# ProPrj_esp32s3-ai-chat_audio_2024-08-31.net
KiCad netlist of a schematic drawn in EasyEDA Pro
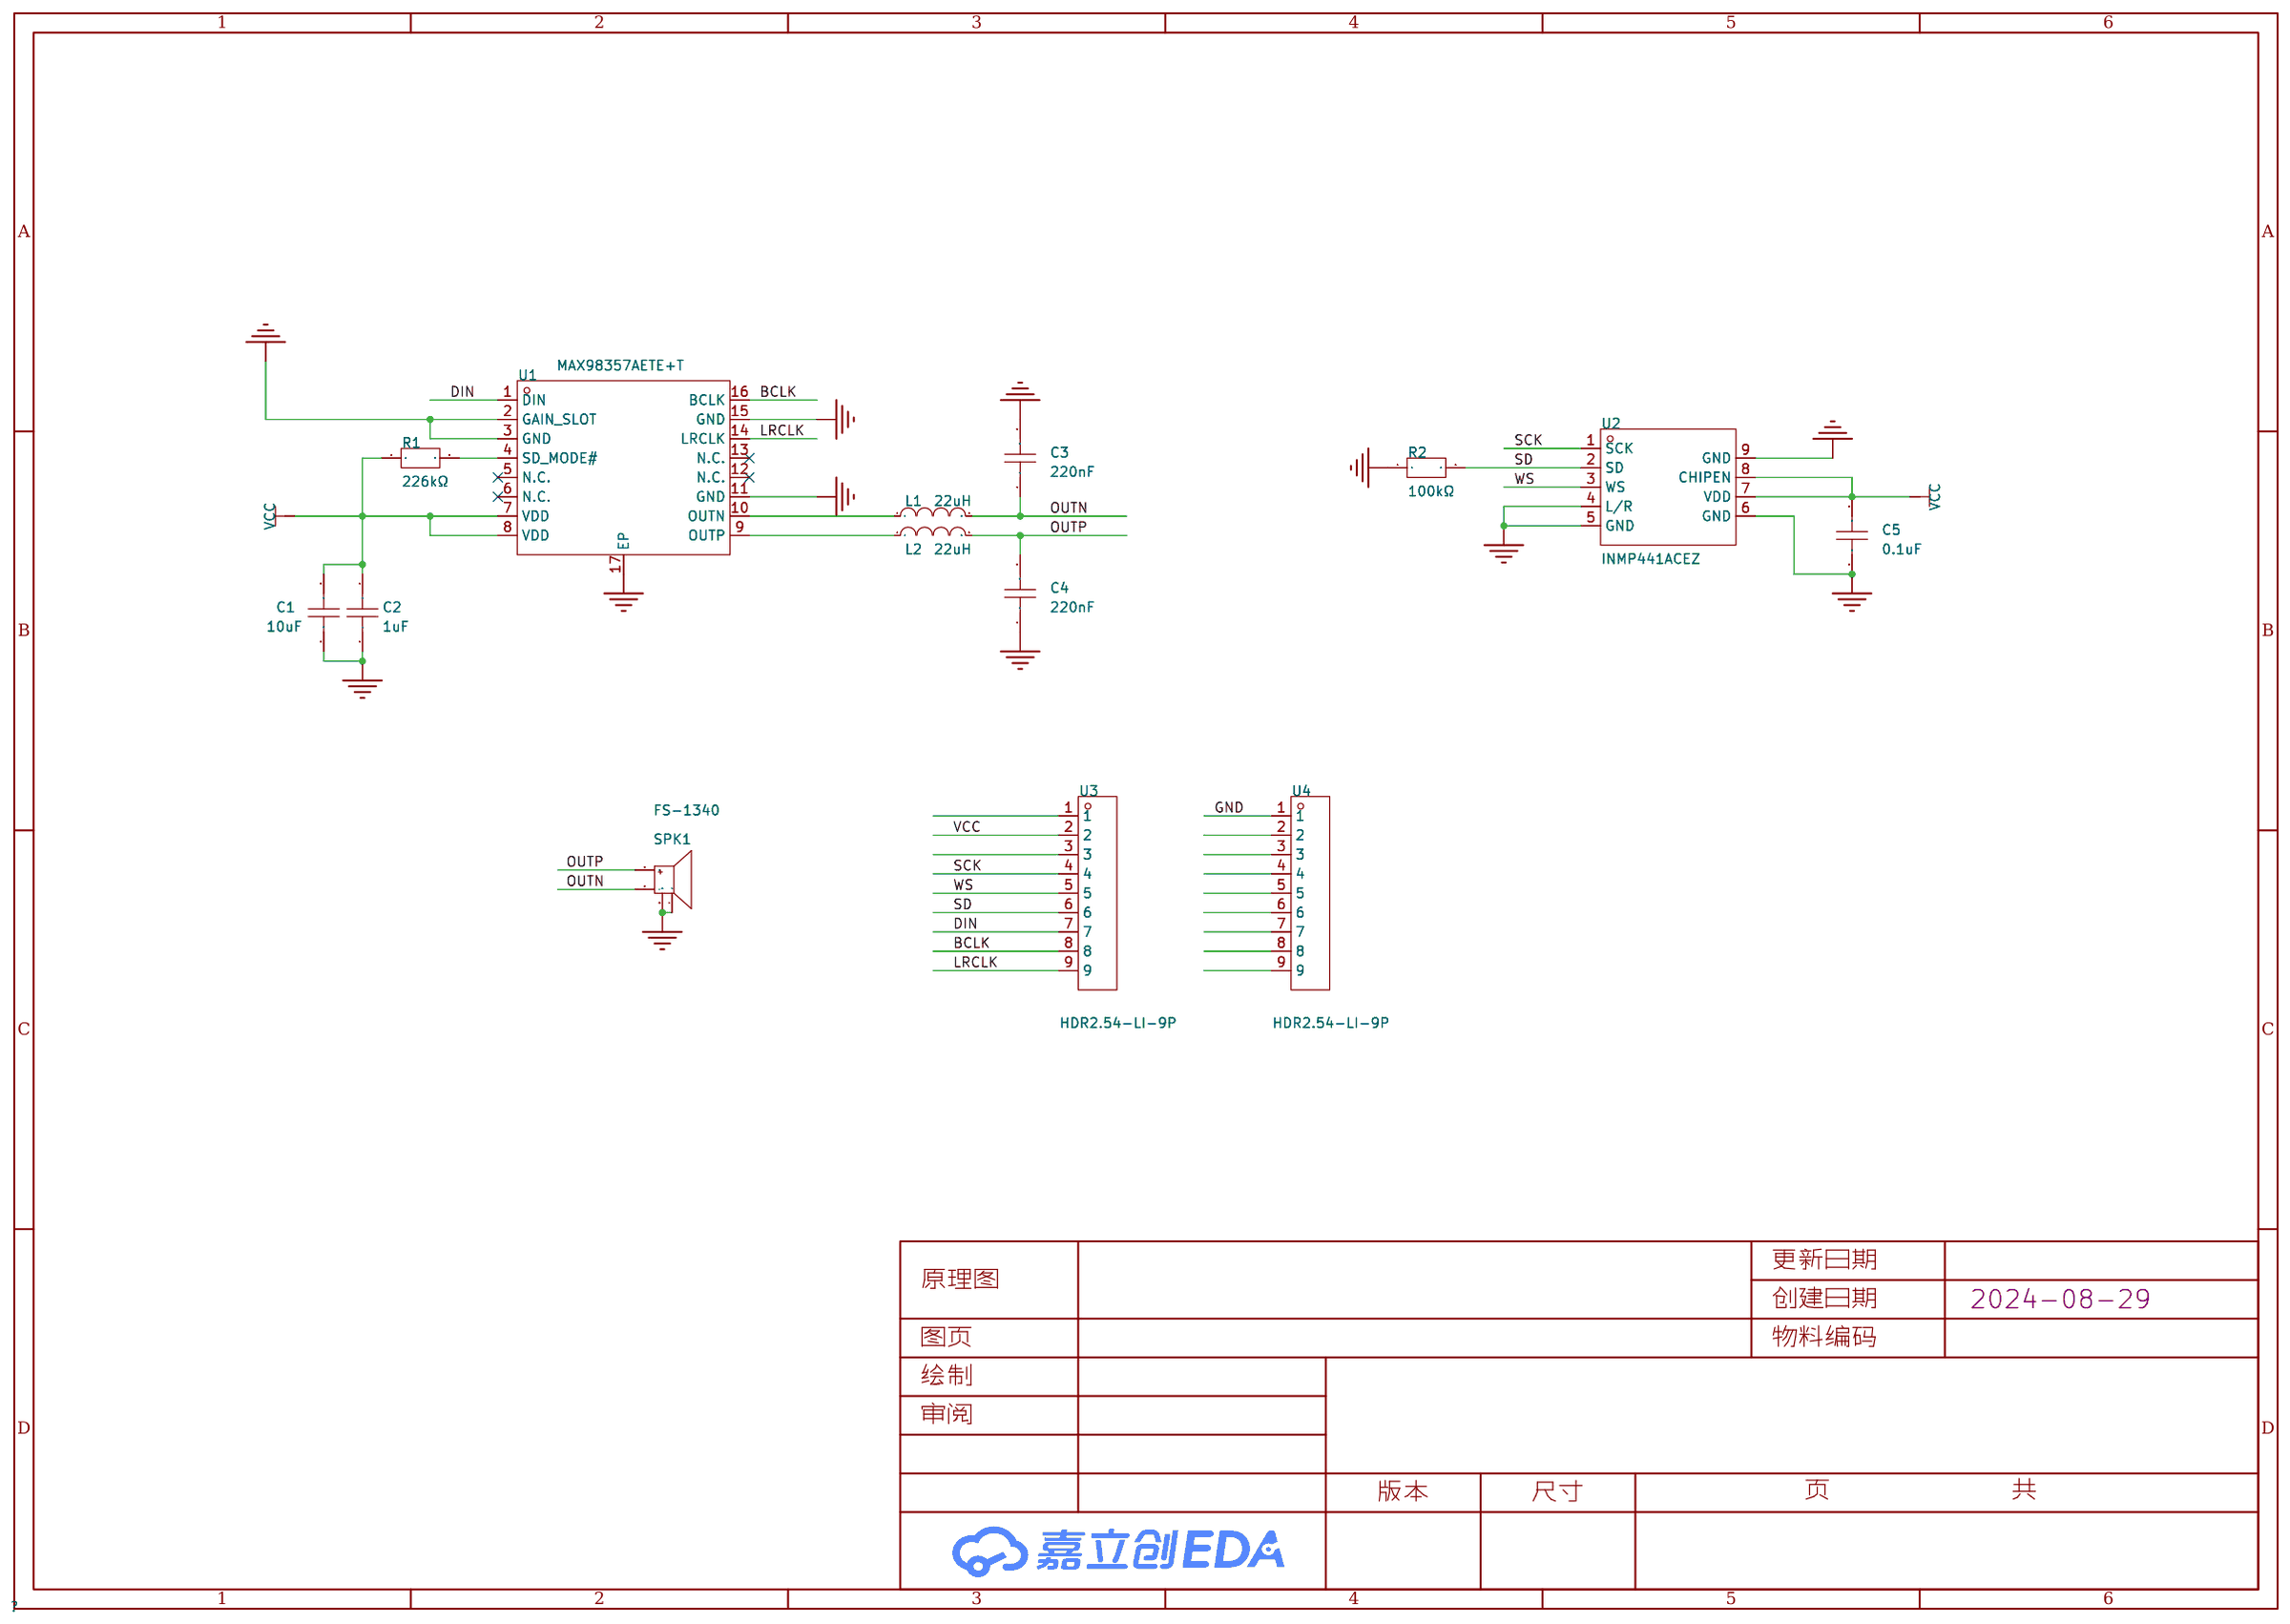
[diagram p0: schematic sheet]

(export (version "E")
  (design (tool "Eeschema 10.0.6"))
  (components
    (comp (ref "C1")
      (value "10uF")
      (footprint "easyedapro:C0603")
      (description "容值:10uF;精度:±20%;额定电压:10V;材质(温度系数):X6S;")
      (fields
        (field (name "Manufacturer Part") "GRT188C81A106ME13J")
        (field (name "Manufacturer") "muRata(村田)")
      )
      (libsource (lib "easyedapro") (part "GRT188C81A106ME13J"))
    )
    (comp (ref "C2")
      (value "1uF")
      (footprint "easyedapro:C0603")
      (description "容值:10uF;精度:±20%;额定电压:10V;材质(温度系数):X6S;")
      (fields
        (field (name "Manufacturer Part") "GRT188C81A106ME13J")
        (field (name "Manufacturer") "muRata(村田)")
      )
      (libsource (lib "easyedapro") (part "GRT188C81A106ME13J"))
    )
    (comp (ref "C3")
      (value "220nF")
      (footprint "easyedapro:C0603")
      (description "容值:10uF;精度:±20%;额定电压:10V;材质(温度系数):X6S;")
      (fields
        (field (name "Manufacturer Part") "GRT188C81A106ME13J")
        (field (name "Manufacturer") "muRata(村田)")
      )
      (libsource (lib "easyedapro") (part "GRT188C81A106ME13J"))
    )
    (comp (ref "C4")
      (value "220nF")
      (footprint "easyedapro:C0603")
      (description "容值:10uF;精度:±20%;额定电压:10V;材质(温度系数):X6S;")
      (fields
        (field (name "Manufacturer Part") "GRT188C81A106ME13J")
        (field (name "Manufacturer") "muRata(村田)")
      )
      (libsource (lib "easyedapro") (part "GRT188C81A106ME13J"))
    )
    (comp (ref "C5")
      (value "0.1uF")
      (footprint "easyedapro:C0603")
      (description "容值:10uF;精度:±20%;额定电压:10V;材质(温度系数):X6S;")
      (fields
        (field (name "Manufacturer Part") "GRT188C81A106ME13J")
        (field (name "Manufacturer") "muRata(村田)")
      )
      (libsource (lib "easyedapro") (part "GRT188C81A106ME13J"))
    )
    (comp (ref "L1")
      (value "22uH")
      (footprint "easyedapro:L0603")
      (description "电感值:22uH;精度:±20%;额定电流:2mA;饱和电流(Isat):-;直流电阻(DCR):1.7Ω;")
      (fields (field (name "Manufacturer Part") "MLF1608C220M") (field (name "Manufacturer") "TDK"))
      (libsource (lib "easyedapro") (part "MLF1608C220M"))
    )
    (comp (ref "L2")
      (value "22uH")
      (footprint "easyedapro:L0603")
      (description "电感值:22uH;精度:±20%;额定电流:2mA;饱和电流(Isat):-;直流电阻(DCR):1.7Ω;")
      (fields (field (name "Manufacturer Part") "MLF1608C220M") (field (name "Manufacturer") "TDK"))
      (libsource (lib "easyedapro") (part "MLF1608C220M"))
    )
    (comp (ref "R1")
      (value "226kΩ")
      (footprint "easyedapro:R0603")
      (description "电阻类型:-;阻值:100kΩ;精度:±5%;功率:200mW;最大工作电压:75V;温度系数:±100ppm/°C;")
      (fields
        (field (name "Manufacturer Part") "HQ03W5J0104T5E")
        (field (name "Manufacturer") "UNI-ROYAL(厚声)")
      )
      (libsource (lib "easyedapro") (part "HQ03W5J0104T5E"))
    )
    (comp (ref "R2")
      (value "100kΩ")
      (footprint "easyedapro:R0603")
      (description "电阻类型:-;阻值:100kΩ;精度:±5%;功率:200mW;最大工作电压:75V;温度系数:±100ppm/°C;")
      (fields
        (field (name "Manufacturer Part") "HQ03W5J0104T5E")
        (field (name "Manufacturer") "UNI-ROYAL(厚声)")
      )
      (libsource (lib "easyedapro") (part "HQ03W5J0104T5E"))
    )
    (comp (ref "SPK1")
      (value "FS-1340")
      (footprint "easyedapro:BUZ-SMD_4P-L13.0-W13.0-P11.4-BL")
      (fields (field (name "Manufacturer") "FUET(福声科技)"))
      (libsource (lib "easyedapro") (part "FS-1340"))
    )
    (comp (ref "U1")
      (value "MAX98357AETE+T")
      (footprint "easyedapro:TQFN-16_L3.0-W3.0-P0.50-BL-EP1.5")
      (description "功放类型:-;扬声器通道数:单声道;输出功率:3.2Wx2@4Ω;")
      (fields (field (name "Manufacturer") "ADI(亚德诺)/MAXIM(美信)"))
      (libsource (lib "easyedapro") (part "MAX98357AETE+T"))
    )
    (comp (ref "U2")
      (value "INMP441ACEZ")
      (footprint "easyedapro:MID-SMD_L4.7-W3.8_INMP441ACEZ")
      (libsource (lib "easyedapro") (part "INMP441ACEZ"))
    )
    (comp (ref "U3")
      (value "HDR2.54-LI-9P")
      (footprint "easyedapro:HDR-TH_9P-P2.54-V-M")
      (libsource (lib "easyedapro") (part "HDR2.54-LI-9P"))
    )
    (comp (ref "U4")
      (value "HDR2.54-LI-9P")
      (footprint "easyedapro:HDR-TH_9P-P2.54-V-M")
      (libsource (lib "easyedapro") (part "HDR2.54-LI-9P"))
    )
  )
  (nets
    (net (code "1") (name "/BCLK") (class "Default")
      (node (ref "U1") (pin "16") (pinfunction "BCLK_16") (pintype "unspecified"))
      (node (ref "U3") (pin "8") (pinfunction "8_8") (pintype "unspecified"))
    )
    (net (code "2") (name "/DIN") (class "Default")
      (node (ref "U1") (pin "1") (pinfunction "DIN_1") (pintype "unspecified"))
      (node (ref "U3") (pin "7") (pinfunction "7_7") (pintype "unspecified"))
    )
    (net (code "3") (name "/LRCLK") (class "Default")
      (node (ref "U1") (pin "14") (pinfunction "LRCLK_14") (pintype "unspecified"))
      (node (ref "U3") (pin "9") (pinfunction "9_9") (pintype "unspecified"))
    )
    (net (code "4") (name "/OUTN") (class "Default")
      (node (ref "C3") (pin "1") (pinfunction "1_1") (pintype "unspecified"))
      (node (ref "L1") (pin "2") (pinfunction "2_2") (pintype "unspecified"))
      (node (ref "SPK1") (pin "2") (pinfunction "-_2") (pintype "input"))
    )
    (net (code "5") (name "/OUTP") (class "Default")
      (node (ref "C4") (pin "2") (pinfunction "2_2") (pintype "unspecified"))
      (node (ref "L2") (pin "2") (pinfunction "2_2") (pintype "unspecified"))
      (node (ref "SPK1") (pin "1") (pinfunction "+_1") (pintype "input"))
    )
    (net (code "6") (name "/SCK") (class "Default")
      (node (ref "U2") (pin "1") (pinfunction "SCK_1") (pintype "unspecified"))
      (node (ref "U3") (pin "4") (pinfunction "4_4") (pintype "unspecified"))
    )
    (net (code "7") (name "/SD") (class "Default")
      (node (ref "R2") (pin "2") (pinfunction "2_2") (pintype "unspecified"))
      (node (ref "U2") (pin "2") (pinfunction "SD_2") (pintype "unspecified"))
      (node (ref "U3") (pin "6") (pinfunction "6_6") (pintype "unspecified"))
    )
    (net (code "8") (name "/WS") (class "Default")
      (node (ref "U2") (pin "3") (pinfunction "WS_3") (pintype "unspecified"))
      (node (ref "U3") (pin "5") (pinfunction "5_5") (pintype "unspecified"))
    )
    (net (code "9") (name "GND") (class "Default")
      (node (ref "C1") (pin "1") (pinfunction "1_1") (pintype "unspecified"))
      (node (ref "C2") (pin "1") (pinfunction "1_1") (pintype "unspecified"))
      (node (ref "C3") (pin "2") (pinfunction "2_2") (pintype "unspecified"))
      (node (ref "C4") (pin "1") (pinfunction "1_1") (pintype "unspecified"))
      (node (ref "C5") (pin "1") (pinfunction "1_1") (pintype "unspecified"))
      (node (ref "R2") (pin "1") (pinfunction "1_1") (pintype "unspecified"))
      (node (ref "SPK1") (pin "3") (pinfunction "3_3") (pintype "input"))
      (node (ref "SPK1") (pin "4") (pinfunction "4_4") (pintype "input"))
      (node (ref "U1") (pin "11") (pinfunction "GND_11") (pintype "unspecified"))
      (node (ref "U1") (pin "15") (pinfunction "GND_15") (pintype "unspecified"))
      (node (ref "U1") (pin "17") (pinfunction "EP_17") (pintype "unspecified"))
      (node (ref "U1") (pin "2") (pinfunction "GAIN_SLOT_2") (pintype "unspecified"))
      (node (ref "U1") (pin "3") (pinfunction "GND_3") (pintype "unspecified"))
      (node (ref "U2") (pin "4") (pinfunction "L/R_4") (pintype "unspecified"))
      (node (ref "U2") (pin "5") (pinfunction "GND_5") (pintype "unspecified"))
      (node (ref "U2") (pin "6") (pinfunction "GND_6") (pintype "unspecified"))
      (node (ref "U2") (pin "9") (pinfunction "GND_9") (pintype "unspecified"))
      (node (ref "U4") (pin "1") (pinfunction "1_1") (pintype "unspecified"))
    )
    (net (code "10") (name "Net-(U1-OUTN)") (class "Default")
      (node (ref "L1") (pin "1") (pinfunction "1_1") (pintype "unspecified"))
      (node (ref "U1") (pin "10") (pinfunction "OUTN_10") (pintype "unspecified"))
    )
    (net (code "11") (name "Net-(U1-OUTP)") (class "Default")
      (node (ref "L2") (pin "1") (pinfunction "1_1") (pintype "unspecified"))
      (node (ref "U1") (pin "9") (pinfunction "OUTP_9") (pintype "unspecified"))
    )
    (net (code "12") (name "Net-(U1-SD_MODE#)") (class "Default")
      (node (ref "R1") (pin "2") (pinfunction "2_2") (pintype "unspecified"))
      (node (ref "U1") (pin "4") (pinfunction "SD_MODE#_4") (pintype "unspecified"))
    )
    (net (code "13") (name "VCC") (class "Default")
      (node (ref "C1") (pin "2") (pinfunction "2_2") (pintype "unspecified"))
      (node (ref "C2") (pin "2") (pinfunction "2_2") (pintype "unspecified"))
      (node (ref "C5") (pin "2") (pinfunction "2_2") (pintype "unspecified"))
      (node (ref "R1") (pin "1") (pinfunction "1_1") (pintype "unspecified"))
      (node (ref "U1") (pin "7") (pinfunction "VDD_7") (pintype "unspecified"))
      (node (ref "U1") (pin "8") (pinfunction "VDD_8") (pintype "unspecified"))
      (node (ref "U2") (pin "7") (pinfunction "VDD_7") (pintype "unspecified"))
      (node (ref "U2") (pin "8") (pinfunction "CHIPEN_8") (pintype "unspecified"))
      (node (ref "U3") (pin "2") (pinfunction "2_2") (pintype "unspecified"))
    )
    (net (code "14") (name "unconnected-(U1-N.C.-Pad5)") (class "Default")
      (node (ref "U1") (pin "5") (pinfunction "N.C._5") (pintype "unspecified+no_connect"))
    )
    (net (code "15") (name "unconnected-(U1-N.C.-Pad6)") (class "Default")
      (node (ref "U1") (pin "6") (pinfunction "N.C._6") (pintype "unspecified+no_connect"))
    )
    (net (code "16") (name "unconnected-(U1-N.C.-Pad12)") (class "Default")
      (node (ref "U1") (pin "12") (pinfunction "N.C._12") (pintype "unspecified+no_connect"))
    )
    (net (code "17") (name "unconnected-(U1-N.C.-Pad13)") (class "Default")
      (node (ref "U1") (pin "13") (pinfunction "N.C._13") (pintype "unspecified+no_connect"))
    )
    (net (code "18") (name "unconnected-(U3-Pad1)") (class "Default")
      (node (ref "U3") (pin "1") (pinfunction "1_1") (pintype "unspecified"))
    )
    (net (code "19") (name "unconnected-(U3-Pad3)") (class "Default")
      (node (ref "U3") (pin "3") (pinfunction "3_3") (pintype "unspecified"))
    )
    (net (code "20") (name "unconnected-(U4-Pad2)") (class "Default")
      (node (ref "U4") (pin "2") (pinfunction "2_2") (pintype "unspecified"))
    )
    (net (code "21") (name "unconnected-(U4-Pad3)") (class "Default")
      (node (ref "U4") (pin "3") (pinfunction "3_3") (pintype "unspecified"))
    )
    (net (code "22") (name "unconnected-(U4-Pad4)") (class "Default")
      (node (ref "U4") (pin "4") (pinfunction "4_4") (pintype "unspecified"))
    )
    (net (code "23") (name "unconnected-(U4-Pad5)") (class "Default")
      (node (ref "U4") (pin "5") (pinfunction "5_5") (pintype "unspecified"))
    )
    (net (code "24") (name "unconnected-(U4-Pad6)") (class "Default")
      (node (ref "U4") (pin "6") (pinfunction "6_6") (pintype "unspecified"))
    )
    (net (code "25") (name "unconnected-(U4-Pad7)") (class "Default")
      (node (ref "U4") (pin "7") (pinfunction "7_7") (pintype "unspecified"))
    )
    (net (code "26") (name "unconnected-(U4-Pad8)") (class "Default")
      (node (ref "U4") (pin "8") (pinfunction "8_8") (pintype "unspecified"))
    )
    (net (code "27") (name "unconnected-(U4-Pad9)") (class "Default")
      (node (ref "U4") (pin "9") (pinfunction "9_9") (pintype "unspecified"))
    )
  )
)
